# 29_LMS7002M_PowerSupply.net
KiCad netlist of a schematic drawn in Altium Designer
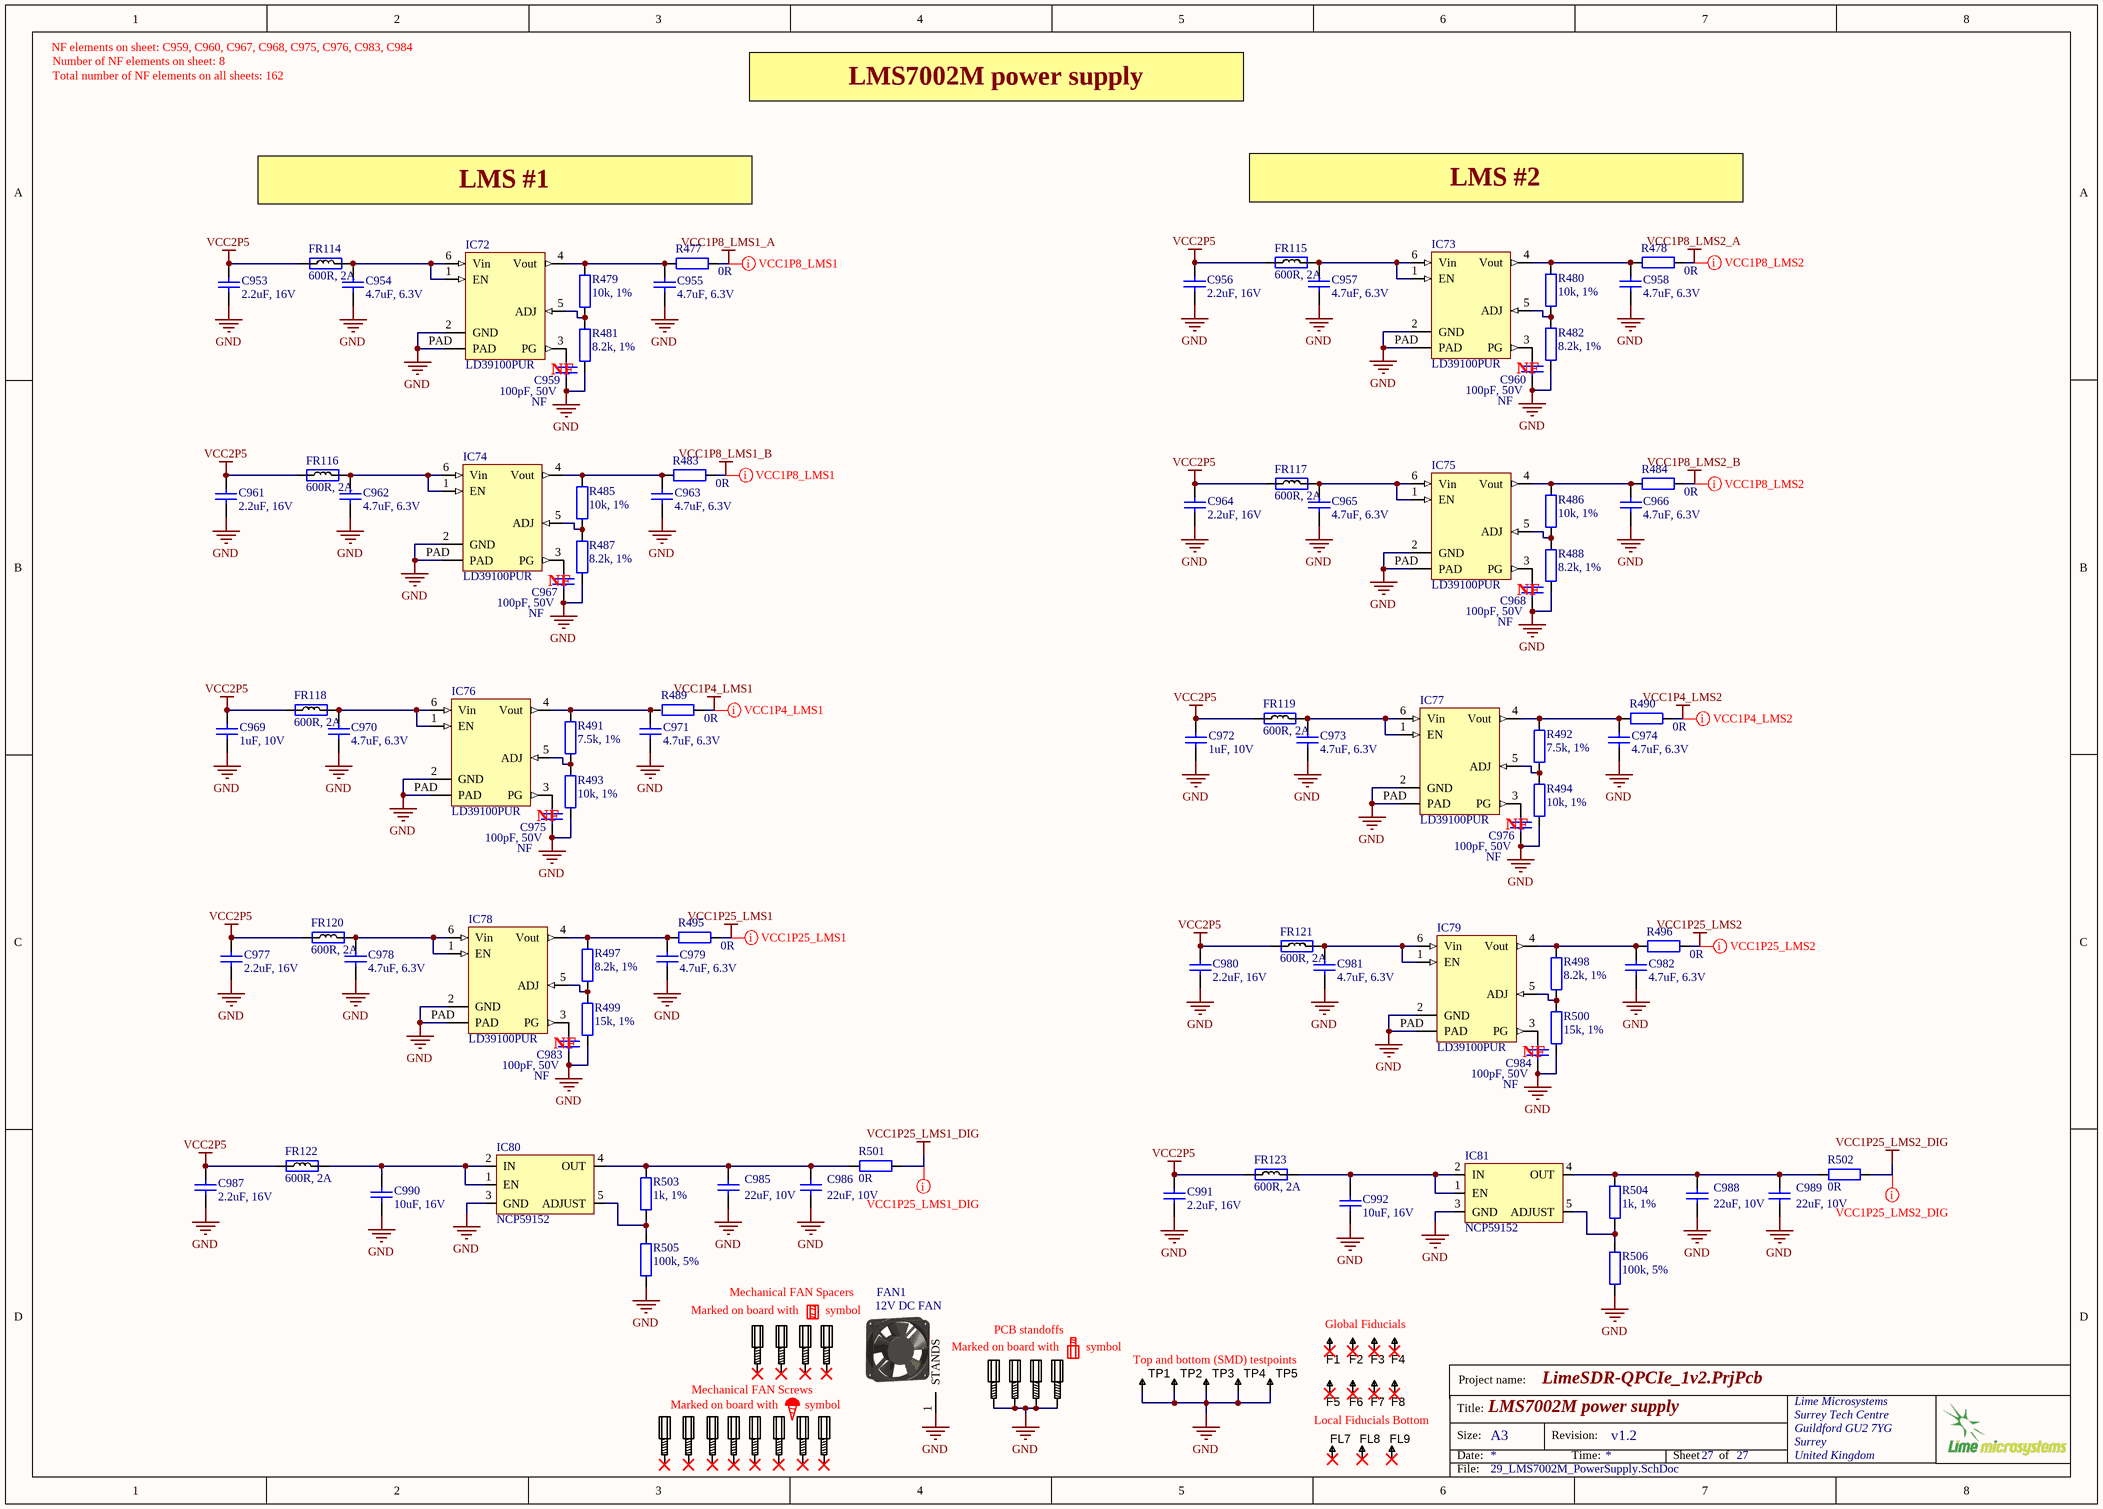
[diagram p0: 29_LMS7002M_PowerSupply.SchDoc]

(export (version "E")
  (design (tool "Eeschema 10.0.6"))
  (components
    (comp (ref "C953")
      (value "2.2uF, 16V")
      (footprint "CAP0402")
      (description "CAP CER 2.2UF 16V 10% X5R 0402")
      (fields (field (name "MANUFACTURER") "TDK Corporation") (field (name "TOLERANCE") "±20%"))
      (libsource (lib "LimeMicroAltiumLib_schLib") (part "Cap_0402"))
    )
    (comp (ref "C954")
      (value "4.7uF, 6.3V")
      (footprint "CAP0402")
      (fields
        (field (name "MANUFACTURER") "Murata Electronics North America")
        (field (name "TOLERANCE") "±20%")
        (field (name "MANUFACTURER PART NUMBER") "GRM155R60J475ME87D")
      )
      (libsource (lib "LimeMicroAltiumLib_schLib") (part "Cap_0402"))
    )
    (comp (ref "C955")
      (value "4.7uF, 6.3V")
      (footprint "CAP0402")
      (fields
        (field (name "MANUFACTURER") "Murata Electronics North America")
        (field (name "TOLERANCE") "±20%")
        (field (name "MANUFACTURER PART NUMBER") "GRM155R60J475ME87D")
      )
      (libsource (lib "LimeMicroAltiumLib_schLib") (part "Cap_0402"))
    )
    (comp (ref "C956")
      (value "2.2uF, 16V")
      (footprint "CAP0402")
      (description "CAP CER 2.2UF 16V 10% X5R 0402")
      (fields (field (name "MANUFACTURER") "TDK Corporation") (field (name "TOLERANCE") "±20%"))
      (libsource (lib "LimeMicroAltiumLib_schLib") (part "Cap_0402"))
    )
    (comp (ref "C957")
      (value "4.7uF, 6.3V")
      (footprint "CAP0402")
      (fields
        (field (name "MANUFACTURER") "Murata Electronics North America")
        (field (name "TOLERANCE") "±20%")
        (field (name "MANUFACTURER PART NUMBER") "GRM155R60J475ME87D")
      )
      (libsource (lib "LimeMicroAltiumLib_schLib") (part "Cap_0402"))
    )
    (comp (ref "C958")
      (value "4.7uF, 6.3V")
      (footprint "CAP0402")
      (fields
        (field (name "MANUFACTURER") "Murata Electronics North America")
        (field (name "TOLERANCE") "±20%")
        (field (name "MANUFACTURER PART NUMBER") "GRM155R60J475ME87D")
      )
      (libsource (lib "LimeMicroAltiumLib_schLib") (part "Cap_0402"))
    )
    (comp (ref "C959")
      (value "100pF, 50V")
      (footprint "CAP0402")
      (fields
        (field (name "ASSEMBLY INFO") "NF")
        (field (name "MANUFACTURER") "Yageo")
        (field (name "TOLERANCE") "±5%")
      )
      (libsource (lib "LimeMicroAltiumLib_schLib") (part "Cap_0402"))
    )
    (comp (ref "C960")
      (value "100pF, 50V")
      (footprint "CAP0402")
      (fields
        (field (name "ASSEMBLY INFO") "NF")
        (field (name "MANUFACTURER") "Yageo")
        (field (name "TOLERANCE") "±5%")
      )
      (libsource (lib "LimeMicroAltiumLib_schLib") (part "Cap_0402"))
    )
    (comp (ref "C961")
      (value "2.2uF, 16V")
      (footprint "CAP0402")
      (description "CAP CER 2.2UF 16V 10% X5R 0402")
      (fields (field (name "MANUFACTURER") "TDK Corporation") (field (name "TOLERANCE") "±20%"))
      (libsource (lib "LimeMicroAltiumLib_schLib") (part "Cap_0402"))
    )
    (comp (ref "C962")
      (value "4.7uF, 6.3V")
      (footprint "CAP0402")
      (fields
        (field (name "MANUFACTURER") "Murata Electronics North America")
        (field (name "TOLERANCE") "±20%")
        (field (name "MANUFACTURER PART NUMBER") "GRM155R60J475ME87D")
      )
      (libsource (lib "LimeMicroAltiumLib_schLib") (part "Cap_0402"))
    )
    (comp (ref "C963")
      (value "4.7uF, 6.3V")
      (footprint "CAP0402")
      (fields
        (field (name "MANUFACTURER") "Murata Electronics North America")
        (field (name "TOLERANCE") "±20%")
        (field (name "MANUFACTURER PART NUMBER") "GRM155R60J475ME87D")
      )
      (libsource (lib "LimeMicroAltiumLib_schLib") (part "Cap_0402"))
    )
    (comp (ref "C964")
      (value "2.2uF, 16V")
      (footprint "CAP0402")
      (description "CAP CER 2.2UF 16V 10% X5R 0402")
      (fields (field (name "MANUFACTURER") "TDK Corporation") (field (name "TOLERANCE") "±20%"))
      (libsource (lib "LimeMicroAltiumLib_schLib") (part "Cap_0402"))
    )
    (comp (ref "C965")
      (value "4.7uF, 6.3V")
      (footprint "CAP0402")
      (fields
        (field (name "MANUFACTURER") "Murata Electronics North America")
        (field (name "TOLERANCE") "±20%")
        (field (name "MANUFACTURER PART NUMBER") "GRM155R60J475ME87D")
      )
      (libsource (lib "LimeMicroAltiumLib_schLib") (part "Cap_0402"))
    )
    (comp (ref "C966")
      (value "4.7uF, 6.3V")
      (footprint "CAP0402")
      (fields
        (field (name "MANUFACTURER") "Murata Electronics North America")
        (field (name "TOLERANCE") "±20%")
        (field (name "MANUFACTURER PART NUMBER") "GRM155R60J475ME87D")
      )
      (libsource (lib "LimeMicroAltiumLib_schLib") (part "Cap_0402"))
    )
    (comp (ref "C967")
      (value "100pF, 50V")
      (footprint "CAP0402")
      (fields
        (field (name "ASSEMBLY INFO") "NF")
        (field (name "MANUFACTURER") "Yageo")
        (field (name "TOLERANCE") "±5%")
      )
      (libsource (lib "LimeMicroAltiumLib_schLib") (part "Cap_0402"))
    )
    (comp (ref "C968")
      (value "100pF, 50V")
      (footprint "CAP0402")
      (fields
        (field (name "ASSEMBLY INFO") "NF")
        (field (name "MANUFACTURER") "Yageo")
        (field (name "TOLERANCE") "±5%")
      )
      (libsource (lib "LimeMicroAltiumLib_schLib") (part "Cap_0402"))
    )
    (comp (ref "C969")
      (value "1uF, 10V")
      (footprint "CAP0402")
      (fields (field (name "MANUFACTURER") "TDK"))
      (libsource (lib "LimeMicroAltiumLib_schLib") (part "Cap_0402"))
    )
    (comp (ref "C970")
      (value "4.7uF, 6.3V")
      (footprint "CAP0402")
      (fields
        (field (name "MANUFACTURER") "Murata Electronics North America")
        (field (name "TOLERANCE") "±20%")
        (field (name "MANUFACTURER PART NUMBER") "GRM155R60J475ME87D")
      )
      (libsource (lib "LimeMicroAltiumLib_schLib") (part "Cap_0402"))
    )
    (comp (ref "C971")
      (value "4.7uF, 6.3V")
      (footprint "CAP0402")
      (fields
        (field (name "MANUFACTURER") "Murata Electronics North America")
        (field (name "TOLERANCE") "±20%")
        (field (name "MANUFACTURER PART NUMBER") "GRM155R60J475ME87D")
      )
      (libsource (lib "LimeMicroAltiumLib_schLib") (part "Cap_0402"))
    )
    (comp (ref "C972")
      (value "1uF, 10V")
      (footprint "CAP0402")
      (fields (field (name "MANUFACTURER") "TDK"))
      (libsource (lib "LimeMicroAltiumLib_schLib") (part "Cap_0402"))
    )
    (comp (ref "C973")
      (value "4.7uF, 6.3V")
      (footprint "CAP0402")
      (fields
        (field (name "MANUFACTURER") "Murata Electronics North America")
        (field (name "TOLERANCE") "±20%")
        (field (name "MANUFACTURER PART NUMBER") "GRM155R60J475ME87D")
      )
      (libsource (lib "LimeMicroAltiumLib_schLib") (part "Cap_0402"))
    )
    (comp (ref "C974")
      (value "4.7uF, 6.3V")
      (footprint "CAP0402")
      (fields
        (field (name "MANUFACTURER") "Murata Electronics North America")
        (field (name "TOLERANCE") "±20%")
        (field (name "MANUFACTURER PART NUMBER") "GRM155R60J475ME87D")
      )
      (libsource (lib "LimeMicroAltiumLib_schLib") (part "Cap_0402"))
    )
    (comp (ref "C975")
      (value "100pF, 50V")
      (footprint "CAP0402")
      (fields
        (field (name "ASSEMBLY INFO") "NF")
        (field (name "MANUFACTURER") "Yageo")
        (field (name "TOLERANCE") "±5%")
      )
      (libsource (lib "LimeMicroAltiumLib_schLib") (part "Cap_0402"))
    )
    (comp (ref "C976")
      (value "100pF, 50V")
      (footprint "CAP0402")
      (fields
        (field (name "ASSEMBLY INFO") "NF")
        (field (name "MANUFACTURER") "Yageo")
        (field (name "TOLERANCE") "±5%")
      )
      (libsource (lib "LimeMicroAltiumLib_schLib") (part "Cap_0402"))
    )
    (comp (ref "C977")
      (value "2.2uF, 16V")
      (footprint "CAP0402")
      (description "CAP CER 2.2UF 16V 10% X5R 0402")
      (fields (field (name "MANUFACTURER") "TDK Corporation") (field (name "TOLERANCE") "±20%"))
      (libsource (lib "LimeMicroAltiumLib_schLib") (part "Cap_0402"))
    )
    (comp (ref "C978")
      (value "4.7uF, 6.3V")
      (footprint "CAP0402")
      (fields
        (field (name "MANUFACTURER") "Murata Electronics North America")
        (field (name "TOLERANCE") "±20%")
        (field (name "MANUFACTURER PART NUMBER") "GRM155R60J475ME87D")
      )
      (libsource (lib "LimeMicroAltiumLib_schLib") (part "Cap_0402"))
    )
    (comp (ref "C979")
      (value "4.7uF, 6.3V")
      (footprint "CAP0402")
      (fields
        (field (name "MANUFACTURER") "Murata Electronics North America")
        (field (name "TOLERANCE") "±20%")
        (field (name "MANUFACTURER PART NUMBER") "GRM155R60J475ME87D")
      )
      (libsource (lib "LimeMicroAltiumLib_schLib") (part "Cap_0402"))
    )
    (comp (ref "C980")
      (value "2.2uF, 16V")
      (footprint "CAP0402")
      (description "CAP CER 2.2UF 16V 10% X5R 0402")
      (fields (field (name "MANUFACTURER") "TDK Corporation") (field (name "TOLERANCE") "±20%"))
      (libsource (lib "LimeMicroAltiumLib_schLib") (part "Cap_0402"))
    )
    (comp (ref "C981")
      (value "4.7uF, 6.3V")
      (footprint "CAP0402")
      (fields
        (field (name "MANUFACTURER") "Murata Electronics North America")
        (field (name "TOLERANCE") "±20%")
        (field (name "MANUFACTURER PART NUMBER") "GRM155R60J475ME87D")
      )
      (libsource (lib "LimeMicroAltiumLib_schLib") (part "Cap_0402"))
    )
    (comp (ref "C982")
      (value "4.7uF, 6.3V")
      (footprint "CAP0402")
      (fields
        (field (name "MANUFACTURER") "Murata Electronics North America")
        (field (name "TOLERANCE") "±20%")
        (field (name "MANUFACTURER PART NUMBER") "GRM155R60J475ME87D")
      )
      (libsource (lib "LimeMicroAltiumLib_schLib") (part "Cap_0402"))
    )
    (comp (ref "C983")
      (value "100pF, 50V")
      (footprint "CAP0402")
      (fields
        (field (name "ASSEMBLY INFO") "NF")
        (field (name "MANUFACTURER") "Yageo")
        (field (name "TOLERANCE") "±5%")
      )
      (libsource (lib "LimeMicroAltiumLib_schLib") (part "Cap_0402"))
    )
    (comp (ref "C984")
      (value "100pF, 50V")
      (footprint "CAP0402")
      (fields
        (field (name "ASSEMBLY INFO") "NF")
        (field (name "MANUFACTURER") "Yageo")
        (field (name "TOLERANCE") "±5%")
      )
      (libsource (lib "LimeMicroAltiumLib_schLib") (part "Cap_0402"))
    )
    (comp (ref "C985")
      (value "22uF, 10V")
      (footprint "CAP0603")
      (fields (field (name "TOLERANCE") "20 %") (field (name "MANUFACTURER") "TDK Corporation"))
      (libsource (lib "LimeFPGAboard_schLib") (part "Cap_0603"))
    )
    (comp (ref "C986")
      (value "22uF, 10V")
      (footprint "CAP0603")
      (fields (field (name "TOLERANCE") "20 %") (field (name "MANUFACTURER") "TDK Corporation"))
      (libsource (lib "LimeFPGAboard_schLib") (part "Cap_0603"))
    )
    (comp (ref "C987")
      (value "2.2uF, 16V")
      (footprint "CAP0402")
      (description "CAP CER 2.2UF 16V 10% X5R 0402")
      (fields (field (name "MANUFACTURER") "TDK Corporation") (field (name "TOLERANCE") "±20%"))
      (libsource (lib "LimeMicroAltiumLib_schLib") (part "Cap_0402"))
    )
    (comp (ref "C988")
      (value "22uF, 10V")
      (footprint "CAP0603")
      (fields (field (name "TOLERANCE") "20 %") (field (name "MANUFACTURER") "TDK Corporation"))
      (libsource (lib "LimeFPGAboard_schLib") (part "Cap_0603"))
    )
    (comp (ref "C989")
      (value "22uF, 10V")
      (footprint "CAP0603")
      (fields (field (name "TOLERANCE") "20 %") (field (name "MANUFACTURER") "TDK Corporation"))
      (libsource (lib "LimeFPGAboard_schLib") (part "Cap_0603"))
    )
    (comp (ref "C990")
      (value "10uF, 16V")
      (footprint "CAP0603")
      (fields (field (name "MANUFACTURER") "Yageo") (field (name "TOLERANCE") "±20%"))
      (libsource (lib "LimeMicroAltiumLib_schLib") (part "Cap_0603"))
    )
    (comp (ref "C991")
      (value "2.2uF, 16V")
      (footprint "CAP0402")
      (description "CAP CER 2.2UF 16V 10% X5R 0402")
      (fields (field (name "MANUFACTURER") "TDK Corporation") (field (name "TOLERANCE") "±20%"))
      (libsource (lib "LimeMicroAltiumLib_schLib") (part "Cap_0402"))
    )
    (comp (ref "C992")
      (value "10uF, 16V")
      (footprint "CAP0603")
      (fields (field (name "MANUFACTURER") "Yageo") (field (name "TOLERANCE") "±20%"))
      (libsource (lib "LimeMicroAltiumLib_schLib") (part "Cap_0603"))
    )
    (comp (ref "F1")
      (value "Fiducial")
      (footprint "Fiducial")
      (libsource (lib "VGTU_Altium_lib") (part "Fiducial"))
    )
    (comp (ref "F2")
      (value "Fiducial")
      (footprint "Fiducial")
      (libsource (lib "VGTU_Altium_lib") (part "Fiducial"))
    )
    (comp (ref "F3")
      (value "Fiducial")
      (footprint "Fiducial")
      (libsource (lib "VGTU_Altium_lib") (part "Fiducial"))
    )
    (comp (ref "F4")
      (value "Fiducial")
      (footprint "Fiducial")
      (libsource (lib "VGTU_Altium_lib") (part "Fiducial"))
    )
    (comp (ref "F5")
      (value "Fiducial")
      (footprint "Fiducial")
      (libsource (lib "VGTU_Altium_lib") (part "Fiducial"))
    )
    (comp (ref "F6")
      (value "Fiducial")
      (footprint "Fiducial")
      (libsource (lib "VGTU_Altium_lib") (part "Fiducial"))
    )
    (comp (ref "F7")
      (value "Fiducial")
      (footprint "Fiducial")
      (libsource (lib "VGTU_Altium_lib") (part "Fiducial"))
    )
    (comp (ref "F8")
      (value "Fiducial")
      (footprint "Fiducial")
      (libsource (lib "VGTU_Altium_lib") (part "Fiducial"))
    )
    (comp (ref "FAN1")
      (value "12V DC FAN")
      (footprint "FAN_60mm_v3")
      (fields (field (name "MANUFACTURER") "Sunon Fans") (field (name ".CHECKED PCB") "AV"))
      (libsource (lib "LimeMicroAltiumLib_schLib") (part "12V_DC_FAN"))
    )
    (comp (ref "FL7")
      (value "Fiducial")
      (footprint "Fiducial_local")
      (libsource (lib "LimeMicroAltiumLib_schLib") (part "Fiducial"))
    )
    (comp (ref "FL8")
      (value "Fiducial")
      (footprint "Fiducial_local")
      (libsource (lib "LimeMicroAltiumLib_schLib") (part "Fiducial"))
    )
    (comp (ref "FL9")
      (value "Fiducial")
      (footprint "Fiducial_local")
      (libsource (lib "LimeMicroAltiumLib_schLib") (part "Fiducial"))
    )
    (comp (ref "FR114")
      (value "600R, 2A")
      (footprint "RES0805")
      (fields (field (name "MANUFACTURER") "TDK"))
      (libsource (lib "LimeMicroAltiumLib_schLib") (part "Ferrite"))
    )
    (comp (ref "FR115")
      (value "600R, 2A")
      (footprint "RES0805")
      (fields (field (name "MANUFACTURER") "TDK"))
      (libsource (lib "LimeMicroAltiumLib_schLib") (part "Ferrite"))
    )
    (comp (ref "FR116")
      (value "600R, 2A")
      (footprint "RES0805")
      (fields (field (name "MANUFACTURER") "TDK"))
      (libsource (lib "LimeMicroAltiumLib_schLib") (part "Ferrite"))
    )
    (comp (ref "FR117")
      (value "600R, 2A")
      (footprint "RES0805")
      (fields (field (name "MANUFACTURER") "TDK"))
      (libsource (lib "LimeMicroAltiumLib_schLib") (part "Ferrite"))
    )
    (comp (ref "FR118")
      (value "600R, 2A")
      (footprint "RES0805")
      (fields (field (name "MANUFACTURER") "TDK"))
      (libsource (lib "LimeMicroAltiumLib_schLib") (part "Ferrite"))
    )
    (comp (ref "FR119")
      (value "600R, 2A")
      (footprint "RES0805")
      (fields (field (name "MANUFACTURER") "TDK"))
      (libsource (lib "LimeMicroAltiumLib_schLib") (part "Ferrite"))
    )
    (comp (ref "FR120")
      (value "600R, 2A")
      (footprint "RES0805")
      (fields (field (name "MANUFACTURER") "TDK"))
      (libsource (lib "LimeMicroAltiumLib_schLib") (part "Ferrite"))
    )
    (comp (ref "FR121")
      (value "600R, 2A")
      (footprint "RES0805")
      (fields (field (name "MANUFACTURER") "TDK"))
      (libsource (lib "LimeMicroAltiumLib_schLib") (part "Ferrite"))
    )
    (comp (ref "FR122")
      (value "600R, 2A")
      (footprint "RES0805")
      (fields (field (name "MANUFACTURER") "TDK"))
      (libsource (lib "LimeMicroAltiumLib_schLib") (part "Ferrite"))
    )
    (comp (ref "FR123")
      (value "600R, 2A")
      (footprint "RES0805")
      (fields (field (name "MANUFACTURER") "TDK"))
      (libsource (lib "LimeMicroAltiumLib_schLib") (part "Ferrite"))
    )
    (comp (ref "IC72")
      (value "LD39100PUR")
      (footprint "LD39100PUR")
      (fields (field (name "MANUFACTURER") "STMicroelectronics"))
      (libsource (lib "LimeMicroAltiumLib_schLib") (part "LD39100PUR"))
    )
    (comp (ref "IC73")
      (value "LD39100PUR")
      (footprint "LD39100PUR")
      (fields (field (name "MANUFACTURER") "STMicroelectronics"))
      (libsource (lib "LimeMicroAltiumLib_schLib") (part "LD39100PUR"))
    )
    (comp (ref "IC74")
      (value "LD39100PUR")
      (footprint "LD39100PUR")
      (fields (field (name "MANUFACTURER") "STMicroelectronics"))
      (libsource (lib "LimeMicroAltiumLib_schLib") (part "LD39100PUR"))
    )
    (comp (ref "IC75")
      (value "LD39100PUR")
      (footprint "LD39100PUR")
      (fields (field (name "MANUFACTURER") "STMicroelectronics"))
      (libsource (lib "LimeMicroAltiumLib_schLib") (part "LD39100PUR"))
    )
    (comp (ref "IC76")
      (value "LD39100PUR")
      (footprint "LD39100PUR")
      (fields (field (name "MANUFACTURER") "STMicroelectronics"))
      (libsource (lib "LimeMicroAltiumLib_schLib") (part "LD39100PUR"))
    )
    (comp (ref "IC77")
      (value "LD39100PUR")
      (footprint "LD39100PUR")
      (fields (field (name "MANUFACTURER") "STMicroelectronics"))
      (libsource (lib "LimeMicroAltiumLib_schLib") (part "LD39100PUR"))
    )
    (comp (ref "IC78")
      (value "LD39100PUR")
      (footprint "LD39100PUR")
      (fields (field (name "MANUFACTURER") "STMicroelectronics"))
      (libsource (lib "LimeMicroAltiumLib_schLib") (part "LD39100PUR"))
    )
    (comp (ref "IC79")
      (value "LD39100PUR")
      (footprint "LD39100PUR")
      (fields (field (name "MANUFACTURER") "STMicroelectronics"))
      (libsource (lib "LimeMicroAltiumLib_schLib") (part "LD39100PUR"))
    )
    (comp (ref "IC80")
      (value "NCP59152")
      (footprint "TO-263-5")
      (fields
        (field (name "MANUFACTURER PART NUMBER") "NCP59152DSADJR4G")
        (field (name "MANUFACTURER") "ON Semiconductor")
      )
      (libsource (lib "LimeMicroAltiumLib_schLib") (part "NCP59151"))
    )
    (comp (ref "IC81")
      (value "NCP59152")
      (footprint "TO-263-5")
      (fields
        (field (name "MANUFACTURER PART NUMBER") "NCP59152DSADJR4G")
        (field (name "MANUFACTURER") "ON Semiconductor")
      )
      (libsource (lib "LimeMicroAltiumLib_schLib") (part "NCP59151"))
    )
    (comp (ref "MECH22")
      (value "Spacer M3")
      (description "STANDOFF M/F MET 5MM HEX 10MM L")
      (fields (field (name "MANUFACTURER") "BOSSARD"))
      (libsource (lib "LimeMicroAltiumLib_schLib") (part "STANDOFF_M-F_THREADED_M3x8x10mm_HEX_5mm dia"))
    )
    (comp (ref "MECH23")
      (value "Spacer M3")
      (description "STANDOFF M/F MET 5MM HEX 10MM L")
      (fields (field (name "MANUFACTURER") "BOSSARD"))
      (libsource (lib "LimeMicroAltiumLib_schLib") (part "STANDOFF_M-F_THREADED_M3x8x10mm_HEX_5mm dia"))
    )
    (comp (ref "MECH24")
      (value "Spacer M3")
      (description "STANDOFF M/F MET 5MM HEX 10MM L")
      (fields (field (name "MANUFACTURER") "BOSSARD"))
      (libsource (lib "LimeMicroAltiumLib_schLib") (part "STANDOFF_M-F_THREADED_M3x8x10mm_HEX_5mm dia"))
    )
    (comp (ref "MECH25")
      (value "Spacer M3")
      (description "STANDOFF M/F MET 5MM HEX 10MM L")
      (fields (field (name "MANUFACTURER") "BOSSARD"))
      (libsource (lib "LimeMicroAltiumLib_schLib") (part "STANDOFF_M-F_THREADED_M3x8x10mm_HEX_5mm dia"))
    )
    (comp (ref "MECH26")
      (value "# pcs.")
      (footprint "PCB_standoff")
      (description "STANDOFF M/F MET 5MM HEX 10MM L")
      (fields (field (name "MANUFACTURER") "Keystone Electronics"))
      (libsource (lib "LimeMicroAltiumLib_schLib") (part "STANDOFF_M-F_THREADED_M3x8x10mm_HEX_5mm dia"))
    )
    (comp (ref "MECH27")
      (value "# pcs.")
      (footprint "PCB_standoff")
      (description "STANDOFF M/F MET 5MM HEX 10MM L")
      (fields (field (name "MANUFACTURER") "Keystone Electronics"))
      (libsource (lib "LimeMicroAltiumLib_schLib") (part "STANDOFF_M-F_THREADED_M3x8x10mm_HEX_5mm dia"))
    )
    (comp (ref "MECH28")
      (value "Screws M3")
      (description "STANDOFF M/F MET 5MM HEX 10MM L")
      (fields (field (name "MANUFACTURER") "BOSSARD"))
      (libsource (lib "LimeMicroAltiumLib_schLib") (part "STANDOFF_M-F_THREADED_M3x8x10mm_HEX_5mm dia"))
    )
    (comp (ref "MECH29")
      (value "Screws M3")
      (description "STANDOFF M/F MET 5MM HEX 10MM L")
      (fields (field (name "MANUFACTURER") "BOSSARD"))
      (libsource (lib "LimeMicroAltiumLib_schLib") (part "STANDOFF_M-F_THREADED_M3x8x10mm_HEX_5mm dia"))
    )
    (comp (ref "MECH30")
      (value "Screws M3")
      (description "STANDOFF M/F MET 5MM HEX 10MM L")
      (fields (field (name "MANUFACTURER") "BOSSARD"))
      (libsource (lib "LimeMicroAltiumLib_schLib") (part "STANDOFF_M-F_THREADED_M3x8x10mm_HEX_5mm dia"))
    )
    (comp (ref "MECH31")
      (value "Screws M3")
      (description "STANDOFF M/F MET 5MM HEX 10MM L")
      (fields (field (name "MANUFACTURER") "BOSSARD"))
      (libsource (lib "LimeMicroAltiumLib_schLib") (part "STANDOFF_M-F_THREADED_M3x8x10mm_HEX_5mm dia"))
    )
    (comp (ref "MECH32")
      (value "Screws M3")
      (description "STANDOFF M/F MET 5MM HEX 10MM L")
      (fields (field (name "MANUFACTURER") "BOSSARD"))
      (libsource (lib "LimeMicroAltiumLib_schLib") (part "STANDOFF_M-F_THREADED_M3x8x10mm_HEX_5mm dia"))
    )
    (comp (ref "MECH33")
      (value "Screws M3")
      (description "STANDOFF M/F MET 5MM HEX 10MM L")
      (fields (field (name "MANUFACTURER") "BOSSARD"))
      (libsource (lib "LimeMicroAltiumLib_schLib") (part "STANDOFF_M-F_THREADED_M3x8x10mm_HEX_5mm dia"))
    )
    (comp (ref "MECH34")
      (value "Screws M3")
      (description "STANDOFF M/F MET 5MM HEX 10MM L")
      (fields (field (name "MANUFACTURER") "BOSSARD"))
      (libsource (lib "LimeMicroAltiumLib_schLib") (part "STANDOFF_M-F_THREADED_M3x8x10mm_HEX_5mm dia"))
    )
    (comp (ref "MECH35")
      (value "Screws M3")
      (description "STANDOFF M/F MET 5MM HEX 10MM L")
      (fields (field (name "MANUFACTURER") "BOSSARD"))
      (libsource (lib "LimeMicroAltiumLib_schLib") (part "STANDOFF_M-F_THREADED_M3x8x10mm_HEX_5mm dia"))
    )
    (comp (ref "MECH36")
      (value "# pcs.")
      (footprint "PCB_standoff")
      (description "STANDOFF M/F MET 5MM HEX 10MM L")
      (fields (field (name "MANUFACTURER") "Keystone Electronics"))
      (libsource (lib "LimeMicroAltiumLib_schLib") (part "STANDOFF_M-F_THREADED_M3x8x10mm_HEX_5mm dia"))
    )
    (comp (ref "MECH37")
      (value "# pcs.")
      (footprint "PCB_standoff")
      (description "STANDOFF M/F MET 5MM HEX 10MM L")
      (fields (field (name "MANUFACTURER") "Keystone Electronics"))
      (libsource (lib "LimeMicroAltiumLib_schLib") (part "STANDOFF_M-F_THREADED_M3x8x10mm_HEX_5mm dia"))
    )
    (comp (ref "R477")
      (value "0R")
      (footprint "RES0402")
      (fields (field (name "MANUFACTURER") "Yageo") (field (name "TOLERANCE") "Jumper"))
      (libsource (lib "LimeMicroAltiumLib_schLib") (part "Res_0402"))
    )
    (comp (ref "R478")
      (value "0R")
      (footprint "RES0402")
      (fields (field (name "MANUFACTURER") "Yageo") (field (name "TOLERANCE") "Jumper"))
      (libsource (lib "LimeMicroAltiumLib_schLib") (part "Res_0402"))
    )
    (comp (ref "R479")
      (value "10k, 1%")
      (footprint "RES0402")
      (fields (field (name "MANUFACTURER") "Yageo") (field (name "TOLERANCE") "±1%"))
      (libsource (lib "LimeMicroAltiumLib_schLib") (part "Res_0402"))
    )
    (comp (ref "R480")
      (value "10k, 1%")
      (footprint "RES0402")
      (fields (field (name "MANUFACTURER") "Yageo") (field (name "TOLERANCE") "±1%"))
      (libsource (lib "LimeMicroAltiumLib_schLib") (part "Res_0402"))
    )
    (comp (ref "R481")
      (value "8.2k, 1%")
      (footprint "RES0402")
      (fields (field (name "MANUFACTURER") "Yageo") (field (name "TOLERANCE") "±1%"))
      (libsource (lib "LimeMicroAltiumLib_schLib") (part "Res_0402"))
    )
    (comp (ref "R482")
      (value "8.2k, 1%")
      (footprint "RES0402")
      (fields (field (name "MANUFACTURER") "Yageo") (field (name "TOLERANCE") "±1%"))
      (libsource (lib "LimeMicroAltiumLib_schLib") (part "Res_0402"))
    )
    (comp (ref "R483")
      (value "0R")
      (footprint "RES0402")
      (fields (field (name "MANUFACTURER") "Yageo") (field (name "TOLERANCE") "Jumper"))
      (libsource (lib "LimeMicroAltiumLib_schLib") (part "Res_0402"))
    )
    (comp (ref "R484")
      (value "0R")
      (footprint "RES0402")
      (fields (field (name "MANUFACTURER") "Yageo") (field (name "TOLERANCE") "Jumper"))
      (libsource (lib "LimeMicroAltiumLib_schLib") (part "Res_0402"))
    )
    (comp (ref "R485")
      (value "10k, 1%")
      (footprint "RES0402")
      (fields (field (name "MANUFACTURER") "Yageo") (field (name "TOLERANCE") "±1%"))
      (libsource (lib "LimeMicroAltiumLib_schLib") (part "Res_0402"))
    )
    (comp (ref "R486")
      (value "10k, 1%")
      (footprint "RES0402")
      (fields (field (name "MANUFACTURER") "Yageo") (field (name "TOLERANCE") "±1%"))
      (libsource (lib "LimeMicroAltiumLib_schLib") (part "Res_0402"))
    )
    (comp (ref "R487")
      (value "8.2k, 1%")
      (footprint "RES0402")
      (fields (field (name "MANUFACTURER") "Yageo") (field (name "TOLERANCE") "±1%"))
      (libsource (lib "LimeMicroAltiumLib_schLib") (part "Res_0402"))
    )
    (comp (ref "R488")
      (value "8.2k, 1%")
      (footprint "RES0402")
      (fields (field (name "MANUFACTURER") "Yageo") (field (name "TOLERANCE") "±1%"))
      (libsource (lib "LimeMicroAltiumLib_schLib") (part "Res_0402"))
    )
    (comp (ref "R489")
      (value "0R")
      (footprint "RES0402")
      (fields (field (name "MANUFACTURER") "Yageo") (field (name "TOLERANCE") "Jumper"))
      (libsource (lib "LimeMicroAltiumLib_schLib") (part "Res_0402"))
    )
    (comp (ref "R490")
      (value "0R")
      (footprint "RES0402")
      (fields (field (name "MANUFACTURER") "Yageo") (field (name "TOLERANCE") "Jumper"))
      (libsource (lib "LimeMicroAltiumLib_schLib") (part "Res_0402"))
    )
    (comp (ref "R491")
      (value "7.5k, 1%")
      (footprint "RES0402")
      (fields
        (field (name "MANUFACTURER") "Yageo")
        (field (name "TOLERANCE") "±1%")
        (field (name "MANUFACTURER PART NUMBER") "RC0402FR-077K5L")
      )
      (libsource (lib "LimeMicroAltiumLib_schLib") (part "Res_0402"))
    )
    (comp (ref "R492")
      (value "7.5k, 1%")
      (footprint "RES0402")
      (fields
        (field (name "MANUFACTURER") "Yageo")
        (field (name "TOLERANCE") "±1%")
        (field (name "MANUFACTURER PART NUMBER") "RC0402FR-077K5L")
      )
      (libsource (lib "LimeMicroAltiumLib_schLib") (part "Res_0402"))
    )
    (comp (ref "R493")
      (value "10k, 1%")
      (footprint "RES0402")
      (fields (field (name "MANUFACTURER") "Yageo") (field (name "TOLERANCE") "±1%"))
      (libsource (lib "LimeMicroAltiumLib_schLib") (part "Res_0402"))
    )
    (comp (ref "R494")
      (value "10k, 1%")
      (footprint "RES0402")
      (fields (field (name "MANUFACTURER") "Yageo") (field (name "TOLERANCE") "±1%"))
      (libsource (lib "LimeMicroAltiumLib_schLib") (part "Res_0402"))
    )
    (comp (ref "R495")
      (value "0R")
      (footprint "RES0402")
      (fields (field (name "MANUFACTURER") "Yageo") (field (name "TOLERANCE") "Jumper"))
      (libsource (lib "LimeMicroAltiumLib_schLib") (part "Res_0402"))
    )
    (comp (ref "R496")
      (value "0R")
      (footprint "RES0402")
      (fields (field (name "MANUFACTURER") "Yageo") (field (name "TOLERANCE") "Jumper"))
      (libsource (lib "LimeMicroAltiumLib_schLib") (part "Res_0402"))
    )
    (comp (ref "R497")
      (value "8.2k, 1%")
      (footprint "RES0402")
      (fields (field (name "MANUFACTURER") "Yageo") (field (name "TOLERANCE") "±1%"))
      (libsource (lib "LimeMicroAltiumLib_schLib") (part "Res_0402"))
    )
    (comp (ref "R498")
      (value "8.2k, 1%")
      (footprint "RES0402")
      (fields (field (name "MANUFACTURER") "Yageo") (field (name "TOLERANCE") "±1%"))
      (libsource (lib "LimeMicroAltiumLib_schLib") (part "Res_0402"))
    )
    (comp (ref "R499")
      (value "15k, 1%")
      (footprint "RES0402")
      (fields (field (name "TOLERANCE") "±1%") (field (name "MANUFACTURER") "Yageo"))
      (libsource (lib "LimeMicroAltiumLib_schLib") (part "Res_0402"))
    )
    (comp (ref "R500")
      (value "15k, 1%")
      (footprint "RES0402")
      (fields (field (name "TOLERANCE") "±1%") (field (name "MANUFACTURER") "Yageo"))
      (libsource (lib "LimeMicroAltiumLib_schLib") (part "Res_0402"))
    )
    (comp (ref "R501")
      (value "0R")
      (footprint "RES0402")
      (fields (field (name "MANUFACTURER") "Yageo") (field (name "TOLERANCE") "Jumper"))
      (libsource (lib "LimeMicroAltiumLib_schLib") (part "Res_0402"))
    )
    (comp (ref "R502")
      (value "0R")
      (footprint "RES0402")
      (fields (field (name "MANUFACTURER") "Yageo") (field (name "TOLERANCE") "Jumper"))
      (libsource (lib "LimeMicroAltiumLib_schLib") (part "Res_0402"))
    )
    (comp (ref "R503")
      (value "1k, 1%")
      (footprint "RES0402")
      (fields (field (name "MANUFACTURER") "Stackpole Electronics Inc") (field (name "TOLERANCE") "±1%"))
      (libsource (lib "LimeMicroAltiumLib_schLib") (part "Res_0402"))
    )
    (comp (ref "R504")
      (value "1k, 1%")
      (footprint "RES0402")
      (fields (field (name "MANUFACTURER") "Stackpole Electronics Inc") (field (name "TOLERANCE") "±1%"))
      (libsource (lib "LimeMicroAltiumLib_schLib") (part "Res_0402"))
    )
    (comp (ref "R505")
      (value "100k, 5%")
      (footprint "RES0402")
      (fields
        (field (name "MANUFACTURER") "Panasonic Electronic Components")
        (field (name "TOLERANCE") "±5%")
      )
      (libsource (lib "LimeMicroAltiumLib_schLib") (part "Res_0402"))
    )
    (comp (ref "R506")
      (value "100k, 5%")
      (footprint "RES0402")
      (fields
        (field (name "MANUFACTURER") "Panasonic Electronic Components")
        (field (name "TOLERANCE") "±5%")
      )
      (libsource (lib "LimeMicroAltiumLib_schLib") (part "Res_0402"))
    )
    (comp (ref "TP1")
      (value "TESTPOINT_THT_MINI")
      (footprint "TP-SMD-LOW_PROFILE")
      (description "Test Point PCB mount Miniature White")
      (fields (field (name "MANUFACTURER") "Harwin Inc"))
      (libsource (lib "LimeMicroAltiumLib_schLib") (part "TESTPOINT_THT_MINI"))
    )
    (comp (ref "TP2")
      (value "TESTPOINT_THT_MINI")
      (footprint "TP-SMD-LOW_PROFILE")
      (description "Test Point PCB mount Miniature White")
      (fields (field (name "MANUFACTURER") "Harwin Inc"))
      (libsource (lib "LimeMicroAltiumLib_schLib") (part "TESTPOINT_THT_MINI"))
    )
    (comp (ref "TP3")
      (value "TESTPOINT_THT_MINI")
      (footprint "TP-SMD-LOW_PROFILE")
      (description "Test Point PCB mount Miniature White")
      (fields (field (name "MANUFACTURER") "Harwin Inc"))
      (libsource (lib "LimeMicroAltiumLib_schLib") (part "TESTPOINT_THT_MINI"))
    )
    (comp (ref "TP4")
      (value "TESTPOINT_THT_MINI")
      (footprint "TP-SMD-LOW_PROFILE")
      (description "Test Point PCB mount Miniature White")
      (fields (field (name "MANUFACTURER") "Harwin Inc"))
      (libsource (lib "LimeMicroAltiumLib_schLib") (part "TESTPOINT_THT_MINI"))
    )
    (comp (ref "TP5")
      (value "TESTPOINT_THT_MINI")
      (footprint "TP-SMD-LOW_PROFILE")
      (description "Test Point PCB mount Miniature White")
      (fields (field (name "MANUFACTURER") "Harwin Inc"))
      (libsource (lib "LimeMicroAltiumLib_schLib") (part "TESTPOINT_THT_MINI"))
    )
  )
  (nets
    (net (code "1") (name "GND") (class "Default")
      (node (ref "C953") (pin "1") (pinfunction "1_1") (pintype "passive"))
      (node (ref "C954") (pin "1") (pinfunction "1_1") (pintype "passive"))
      (node (ref "C955") (pin "1") (pinfunction "1_1") (pintype "passive"))
      (node (ref "C956") (pin "1") (pinfunction "1_1") (pintype "passive"))
      (node (ref "C957") (pin "1") (pinfunction "1_1") (pintype "passive"))
      (node (ref "C958") (pin "1") (pinfunction "1_1") (pintype "passive"))
      (node (ref "C959") (pin "1") (pinfunction "1_1") (pintype "passive"))
      (node (ref "C960") (pin "1") (pinfunction "1_1") (pintype "passive"))
      (node (ref "C961") (pin "1") (pinfunction "1_1") (pintype "passive"))
      (node (ref "C962") (pin "1") (pinfunction "1_1") (pintype "passive"))
      (node (ref "C963") (pin "1") (pinfunction "1_1") (pintype "passive"))
      (node (ref "C964") (pin "1") (pinfunction "1_1") (pintype "passive"))
      (node (ref "C965") (pin "1") (pinfunction "1_1") (pintype "passive"))
      (node (ref "C966") (pin "1") (pinfunction "1_1") (pintype "passive"))
      (node (ref "C967") (pin "1") (pinfunction "1_1") (pintype "passive"))
      (node (ref "C968") (pin "1") (pinfunction "1_1") (pintype "passive"))
      (node (ref "C969") (pin "1") (pinfunction "1_1") (pintype "passive"))
      (node (ref "C970") (pin "1") (pinfunction "1_1") (pintype "passive"))
      (node (ref "C971") (pin "1") (pinfunction "1_1") (pintype "passive"))
      (node (ref "C972") (pin "1") (pinfunction "1_1") (pintype "passive"))
      (node (ref "C973") (pin "1") (pinfunction "1_1") (pintype "passive"))
      (node (ref "C974") (pin "1") (pinfunction "1_1") (pintype "passive"))
      (node (ref "C975") (pin "1") (pinfunction "1_1") (pintype "passive"))
      (node (ref "C976") (pin "1") (pinfunction "1_1") (pintype "passive"))
      (node (ref "C977") (pin "1") (pinfunction "1_1") (pintype "passive"))
      (node (ref "C978") (pin "1") (pinfunction "1_1") (pintype "passive"))
      (node (ref "C979") (pin "1") (pinfunction "1_1") (pintype "passive"))
      (node (ref "C980") (pin "1") (pinfunction "1_1") (pintype "passive"))
      (node (ref "C981") (pin "1") (pinfunction "1_1") (pintype "passive"))
      (node (ref "C982") (pin "1") (pinfunction "1_1") (pintype "passive"))
      (node (ref "C983") (pin "1") (pinfunction "1_1") (pintype "passive"))
      (node (ref "C984") (pin "1") (pinfunction "1_1") (pintype "passive"))
      (node (ref "C985") (pin "1") (pinfunction "1_1") (pintype "passive"))
      (node (ref "C986") (pin "1") (pinfunction "1_1") (pintype "passive"))
      (node (ref "C987") (pin "1") (pinfunction "1_1") (pintype "passive"))
      (node (ref "C988") (pin "1") (pinfunction "1_1") (pintype "passive"))
      (node (ref "C989") (pin "1") (pinfunction "1_1") (pintype "passive"))
      (node (ref "C990") (pin "1") (pinfunction "1_1") (pintype "passive"))
      (node (ref "C991") (pin "1") (pinfunction "1_1") (pintype "passive"))
      (node (ref "C992") (pin "1") (pinfunction "1_1") (pintype "passive"))
      (node (ref "FAN1") (pin "1") (pinfunction "STANDS_1") (pintype "passive"))
      (node (ref "IC72") (pin "2") (pinfunction "GND_2") (pintype "passive"))
      (node (ref "IC72") (pin "PAD") (pinfunction "PAD_PAD") (pintype "passive"))
      (node (ref "IC73") (pin "2") (pinfunction "GND_2") (pintype "passive"))
      (node (ref "IC73") (pin "PAD") (pinfunction "PAD_PAD") (pintype "passive"))
      (node (ref "IC74") (pin "2") (pinfunction "GND_2") (pintype "passive"))
      (node (ref "IC74") (pin "PAD") (pinfunction "PAD_PAD") (pintype "passive"))
      (node (ref "IC75") (pin "2") (pinfunction "GND_2") (pintype "passive"))
      (node (ref "IC75") (pin "PAD") (pinfunction "PAD_PAD") (pintype "passive"))
      (node (ref "IC76") (pin "2") (pinfunction "GND_2") (pintype "passive"))
      (node (ref "IC76") (pin "PAD") (pinfunction "PAD_PAD") (pintype "passive"))
      (node (ref "IC77") (pin "2") (pinfunction "GND_2") (pintype "passive"))
      (node (ref "IC77") (pin "PAD") (pinfunction "PAD_PAD") (pintype "passive"))
      (node (ref "IC78") (pin "2") (pinfunction "GND_2") (pintype "passive"))
      (node (ref "IC78") (pin "PAD") (pinfunction "PAD_PAD") (pintype "passive"))
      (node (ref "IC79") (pin "2") (pinfunction "GND_2") (pintype "passive"))
      (node (ref "IC79") (pin "PAD") (pinfunction "PAD_PAD") (pintype "passive"))
      (node (ref "IC80") (pin "3") (pinfunction "GND_3") (pintype "passive"))
      (node (ref "IC81") (pin "3") (pinfunction "GND_3") (pintype "passive"))
      (node (ref "MECH26") (pin "MH1") (pinfunction "MH1_MH1") (pintype "passive"))
      (node (ref "MECH27") (pin "MH1") (pinfunction "MH1_MH1") (pintype "passive"))
      (node (ref "MECH36") (pin "MH1") (pinfunction "MH1_MH1") (pintype "passive"))
      (node (ref "MECH37") (pin "MH1") (pinfunction "MH1_MH1") (pintype "passive"))
      (node (ref "R481") (pin "1") (pinfunction "1_1") (pintype "passive"))
      (node (ref "R482") (pin "1") (pinfunction "1_1") (pintype "passive"))
      (node (ref "R487") (pin "1") (pinfunction "1_1") (pintype "passive"))
      (node (ref "R488") (pin "1") (pinfunction "1_1") (pintype "passive"))
      (node (ref "R493") (pin "1") (pinfunction "1_1") (pintype "passive"))
      (node (ref "R494") (pin "1") (pinfunction "1_1") (pintype "passive"))
      (node (ref "R499") (pin "1") (pinfunction "1_1") (pintype "passive"))
      (node (ref "R500") (pin "1") (pinfunction "1_1") (pintype "passive"))
      (node (ref "R505") (pin "2") (pinfunction "2_2") (pintype "passive"))
      (node (ref "R506") (pin "2") (pinfunction "2_2") (pintype "passive"))
      (node (ref "TP1") (pin "1") (pintype "passive"))
      (node (ref "TP2") (pin "1") (pintype "passive"))
      (node (ref "TP3") (pin "1") (pintype "passive"))
      (node (ref "TP4") (pin "1") (pintype "passive"))
      (node (ref "TP5") (pin "1") (pintype "passive"))
    )
    (net (code "2") (name "Net-(IC72-ADJ)") (class "Default")
      (node (ref "IC72") (pin "5") (pinfunction "ADJ_5") (pintype "input"))
      (node (ref "R479") (pin "1") (pinfunction "1_1") (pintype "passive"))
      (node (ref "R481") (pin "2") (pinfunction "2_2") (pintype "passive"))
    )
    (net (code "3") (name "Net-(IC72-EN)") (class "Default")
      (node (ref "C954") (pin "2") (pinfunction "2_2") (pintype "passive"))
      (node (ref "FR114") (pin "2") (pinfunction "2_2") (pintype "passive"))
      (node (ref "IC72") (pin "1") (pinfunction "EN_1") (pintype "input"))
      (node (ref "IC72") (pin "6") (pinfunction "Vin_6") (pintype "input"))
    )
    (net (code "4") (name "Net-(IC72-PG)") (class "Default")
      (node (ref "C959") (pin "2") (pinfunction "2_2") (pintype "passive"))
      (node (ref "IC72") (pin "3") (pinfunction "PG_3") (pintype "output"))
    )
    (net (code "5") (name "Net-(IC72-Vout)") (class "Default")
      (node (ref "C955") (pin "2") (pinfunction "2_2") (pintype "passive"))
      (node (ref "IC72") (pin "4") (pinfunction "Vout_4") (pintype "output"))
      (node (ref "R477") (pin "2") (pinfunction "2_2") (pintype "passive"))
      (node (ref "R479") (pin "2") (pinfunction "2_2") (pintype "passive"))
    )
    (net (code "6") (name "Net-(IC73-ADJ)") (class "Default")
      (node (ref "IC73") (pin "5") (pinfunction "ADJ_5") (pintype "input"))
      (node (ref "R480") (pin "1") (pinfunction "1_1") (pintype "passive"))
      (node (ref "R482") (pin "2") (pinfunction "2_2") (pintype "passive"))
    )
    (net (code "7") (name "Net-(IC73-EN)") (class "Default")
      (node (ref "C957") (pin "2") (pinfunction "2_2") (pintype "passive"))
      (node (ref "FR115") (pin "2") (pinfunction "2_2") (pintype "passive"))
      (node (ref "IC73") (pin "1") (pinfunction "EN_1") (pintype "input"))
      (node (ref "IC73") (pin "6") (pinfunction "Vin_6") (pintype "input"))
    )
    (net (code "8") (name "Net-(IC73-PG)") (class "Default")
      (node (ref "C960") (pin "2") (pinfunction "2_2") (pintype "passive"))
      (node (ref "IC73") (pin "3") (pinfunction "PG_3") (pintype "output"))
    )
    (net (code "9") (name "Net-(IC73-Vout)") (class "Default")
      (node (ref "C958") (pin "2") (pinfunction "2_2") (pintype "passive"))
      (node (ref "IC73") (pin "4") (pinfunction "Vout_4") (pintype "output"))
      (node (ref "R478") (pin "2") (pinfunction "2_2") (pintype "passive"))
      (node (ref "R480") (pin "2") (pinfunction "2_2") (pintype "passive"))
    )
    (net (code "10") (name "Net-(IC74-ADJ)") (class "Default")
      (node (ref "IC74") (pin "5") (pinfunction "ADJ_5") (pintype "input"))
      (node (ref "R485") (pin "1") (pinfunction "1_1") (pintype "passive"))
      (node (ref "R487") (pin "2") (pinfunction "2_2") (pintype "passive"))
    )
    (net (code "11") (name "Net-(IC74-EN)") (class "Default")
      (node (ref "C962") (pin "2") (pinfunction "2_2") (pintype "passive"))
      (node (ref "FR116") (pin "2") (pinfunction "2_2") (pintype "passive"))
      (node (ref "IC74") (pin "1") (pinfunction "EN_1") (pintype "input"))
      (node (ref "IC74") (pin "6") (pinfunction "Vin_6") (pintype "input"))
    )
    (net (code "12") (name "Net-(IC74-PG)") (class "Default")
      (node (ref "C967") (pin "2") (pinfunction "2_2") (pintype "passive"))
      (node (ref "IC74") (pin "3") (pinfunction "PG_3") (pintype "output"))
    )
    (net (code "13") (name "Net-(IC74-Vout)") (class "Default")
      (node (ref "C963") (pin "2") (pinfunction "2_2") (pintype "passive"))
      (node (ref "IC74") (pin "4") (pinfunction "Vout_4") (pintype "output"))
      (node (ref "R483") (pin "2") (pinfunction "2_2") (pintype "passive"))
      (node (ref "R485") (pin "2") (pinfunction "2_2") (pintype "passive"))
    )
    (net (code "14") (name "Net-(IC75-ADJ)") (class "Default")
      (node (ref "IC75") (pin "5") (pinfunction "ADJ_5") (pintype "input"))
      (node (ref "R486") (pin "1") (pinfunction "1_1") (pintype "passive"))
      (node (ref "R488") (pin "2") (pinfunction "2_2") (pintype "passive"))
    )
    (net (code "15") (name "Net-(IC75-EN)") (class "Default")
      (node (ref "C965") (pin "2") (pinfunction "2_2") (pintype "passive"))
      (node (ref "FR117") (pin "2") (pinfunction "2_2") (pintype "passive"))
      (node (ref "IC75") (pin "1") (pinfunction "EN_1") (pintype "input"))
      (node (ref "IC75") (pin "6") (pinfunction "Vin_6") (pintype "input"))
    )
    (net (code "16") (name "Net-(IC75-PG)") (class "Default")
      (node (ref "C968") (pin "2") (pinfunction "2_2") (pintype "passive"))
      (node (ref "IC75") (pin "3") (pinfunction "PG_3") (pintype "output"))
    )
    (net (code "17") (name "Net-(IC75-Vout)") (class "Default")
      (node (ref "C966") (pin "2") (pinfunction "2_2") (pintype "passive"))
      (node (ref "IC75") (pin "4") (pinfunction "Vout_4") (pintype "output"))
      (node (ref "R484") (pin "2") (pinfunction "2_2") (pintype "passive"))
      (node (ref "R486") (pin "2") (pinfunction "2_2") (pintype "passive"))
    )
    (net (code "18") (name "Net-(IC76-ADJ)") (class "Default")
      (node (ref "IC76") (pin "5") (pinfunction "ADJ_5") (pintype "input"))
      (node (ref "R491") (pin "1") (pinfunction "1_1") (pintype "passive"))
      (node (ref "R493") (pin "2") (pinfunction "2_2") (pintype "passive"))
    )
    (net (code "19") (name "Net-(IC76-EN)") (class "Default")
      (node (ref "C970") (pin "2") (pinfunction "2_2") (pintype "passive"))
      (node (ref "FR118") (pin "2") (pinfunction "2_2") (pintype "passive"))
      (node (ref "IC76") (pin "1") (pinfunction "EN_1") (pintype "input"))
      (node (ref "IC76") (pin "6") (pinfunction "Vin_6") (pintype "input"))
    )
    (net (code "20") (name "Net-(IC76-PG)") (class "Default")
      (node (ref "C975") (pin "2") (pinfunction "2_2") (pintype "passive"))
      (node (ref "IC76") (pin "3") (pinfunction "PG_3") (pintype "output"))
    )
    (net (code "21") (name "Net-(IC76-Vout)") (class "Default")
      (node (ref "C971") (pin "2") (pinfunction "2_2") (pintype "passive"))
      (node (ref "IC76") (pin "4") (pinfunction "Vout_4") (pintype "output"))
      (node (ref "R489") (pin "2") (pinfunction "2_2") (pintype "passive"))
      (node (ref "R491") (pin "2") (pinfunction "2_2") (pintype "passive"))
    )
    (net (code "22") (name "Net-(IC77-ADJ)") (class "Default")
      (node (ref "IC77") (pin "5") (pinfunction "ADJ_5") (pintype "input"))
      (node (ref "R492") (pin "1") (pinfunction "1_1") (pintype "passive"))
      (node (ref "R494") (pin "2") (pinfunction "2_2") (pintype "passive"))
    )
    (net (code "23") (name "Net-(IC77-EN)") (class "Default")
      (node (ref "C973") (pin "2") (pinfunction "2_2") (pintype "passive"))
      (node (ref "FR119") (pin "2") (pinfunction "2_2") (pintype "passive"))
      (node (ref "IC77") (pin "1") (pinfunction "EN_1") (pintype "input"))
      (node (ref "IC77") (pin "6") (pinfunction "Vin_6") (pintype "input"))
    )
    (net (code "24") (name "Net-(IC77-PG)") (class "Default")
      (node (ref "C976") (pin "2") (pinfunction "2_2") (pintype "passive"))
      (node (ref "IC77") (pin "3") (pinfunction "PG_3") (pintype "output"))
    )
    (net (code "25") (name "Net-(IC77-Vout)") (class "Default")
      (node (ref "C974") (pin "2") (pinfunction "2_2") (pintype "passive"))
      (node (ref "IC77") (pin "4") (pinfunction "Vout_4") (pintype "output"))
      (node (ref "R490") (pin "2") (pinfunction "2_2") (pintype "passive"))
      (node (ref "R492") (pin "2") (pinfunction "2_2") (pintype "passive"))
    )
    (net (code "26") (name "Net-(IC78-ADJ)") (class "Default")
      (node (ref "IC78") (pin "5") (pinfunction "ADJ_5") (pintype "input"))
      (node (ref "R497") (pin "1") (pinfunction "1_1") (pintype "passive"))
      (node (ref "R499") (pin "2") (pinfunction "2_2") (pintype "passive"))
    )
    (net (code "27") (name "Net-(IC78-EN)") (class "Default")
      (node (ref "C978") (pin "2") (pinfunction "2_2") (pintype "passive"))
      (node (ref "FR120") (pin "2") (pinfunction "2_2") (pintype "passive"))
      (node (ref "IC78") (pin "1") (pinfunction "EN_1") (pintype "input"))
      (node (ref "IC78") (pin "6") (pinfunction "Vin_6") (pintype "input"))
    )
    (net (code "28") (name "Net-(IC78-PG)") (class "Default")
      (node (ref "C983") (pin "2") (pinfunction "2_2") (pintype "passive"))
      (node (ref "IC78") (pin "3") (pinfunction "PG_3") (pintype "output"))
    )
    (net (code "29") (name "Net-(IC78-Vout)") (class "Default")
      (node (ref "C979") (pin "2") (pinfunction "2_2") (pintype "passive"))
      (node (ref "IC78") (pin "4") (pinfunction "Vout_4") (pintype "output"))
      (node (ref "R495") (pin "2") (pinfunction "2_2") (pintype "passive"))
      (node (ref "R497") (pin "2") (pinfunction "2_2") (pintype "passive"))
    )
    (net (code "30") (name "Net-(IC79-ADJ)") (class "Default")
      (node (ref "IC79") (pin "5") (pinfunction "ADJ_5") (pintype "input"))
      (node (ref "R498") (pin "1") (pinfunction "1_1") (pintype "passive"))
      (node (ref "R500") (pin "2") (pinfunction "2_2") (pintype "passive"))
    )
    (net (code "31") (name "Net-(IC79-EN)") (class "Default")
      (node (ref "C981") (pin "2") (pinfunction "2_2") (pintype "passive"))
      (node (ref "FR121") (pin "2") (pinfunction "2_2") (pintype "passive"))
      (node (ref "IC79") (pin "1") (pinfunction "EN_1") (pintype "input"))
      (node (ref "IC79") (pin "6") (pinfunction "Vin_6") (pintype "input"))
    )
    (net (code "32") (name "Net-(IC79-PG)") (class "Default")
      (node (ref "C984") (pin "2") (pinfunction "2_2") (pintype "passive"))
      (node (ref "IC79") (pin "3") (pinfunction "PG_3") (pintype "output"))
    )
    (net (code "33") (name "Net-(IC79-Vout)") (class "Default")
      (node (ref "C982") (pin "2") (pinfunction "2_2") (pintype "passive"))
      (node (ref "IC79") (pin "4") (pinfunction "Vout_4") (pintype "output"))
      (node (ref "R496") (pin "2") (pinfunction "2_2") (pintype "passive"))
      (node (ref "R498") (pin "2") (pinfunction "2_2") (pintype "passive"))
    )
    (net (code "34") (name "Net-(IC80-ADJUST)") (class "Default")
      (node (ref "IC80") (pin "5") (pinfunction "ADJUST_5") (pintype "input"))
      (node (ref "R503") (pin "1") (pinfunction "1_1") (pintype "passive"))
      (node (ref "R505") (pin "1") (pinfunction "1_1") (pintype "passive"))
    )
    (net (code "35") (name "Net-(IC80-EN)") (class "Default")
      (node (ref "C990") (pin "2") (pinfunction "2_2") (pintype "passive"))
      (node (ref "FR122") (pin "2") (pinfunction "2_2") (pintype "passive"))
      (node (ref "IC80") (pin "1") (pinfunction "EN_1") (pintype "input"))
      (node (ref "IC80") (pin "2") (pinfunction "IN_2") (pintype "input"))
    )
    (net (code "36") (name "Net-(IC80-OUT)") (class "Default")
      (node (ref "C985") (pin "2") (pinfunction "2_2") (pintype "passive"))
      (node (ref "C986") (pin "2") (pinfunction "2_2") (pintype "passive"))
      (node (ref "IC80") (pin "4") (pinfunction "OUT_4") (pintype "output"))
      (node (ref "R501") (pin "2") (pinfunction "2_2") (pintype "passive"))
      (node (ref "R503") (pin "2") (pinfunction "2_2") (pintype "passive"))
    )
    (net (code "37") (name "Net-(IC81-ADJUST)") (class "Default")
      (node (ref "IC81") (pin "5") (pinfunction "ADJUST_5") (pintype "input"))
      (node (ref "R504") (pin "1") (pinfunction "1_1") (pintype "passive"))
      (node (ref "R506") (pin "1") (pinfunction "1_1") (pintype "passive"))
    )
    (net (code "38") (name "Net-(IC81-EN)") (class "Default")
      (node (ref "C992") (pin "2") (pinfunction "2_2") (pintype "passive"))
      (node (ref "FR123") (pin "2") (pinfunction "2_2") (pintype "passive"))
      (node (ref "IC81") (pin "1") (pinfunction "EN_1") (pintype "input"))
      (node (ref "IC81") (pin "2") (pinfunction "IN_2") (pintype "input"))
    )
    (net (code "39") (name "Net-(IC81-OUT)") (class "Default")
      (node (ref "C988") (pin "2") (pinfunction "2_2") (pintype "passive"))
      (node (ref "C989") (pin "2") (pinfunction "2_2") (pintype "passive"))
      (node (ref "IC81") (pin "4") (pinfunction "OUT_4") (pintype "output"))
      (node (ref "R502") (pin "2") (pinfunction "2_2") (pintype "passive"))
      (node (ref "R504") (pin "2") (pinfunction "2_2") (pintype "passive"))
    )
    (net (code "40") (name "VCC1P4_LMS1") (class "Default")
      (node (ref "R489") (pin "1") (pinfunction "1_1") (pintype "passive"))
    )
    (net (code "41") (name "VCC1P4_LMS2") (class "Default")
      (node (ref "R490") (pin "1") (pinfunction "1_1") (pintype "passive"))
    )
    (net (code "42") (name "VCC1P8_LMS1_A") (class "Default")
      (node (ref "R477") (pin "1") (pinfunction "1_1") (pintype "passive"))
    )
    (net (code "43") (name "VCC1P8_LMS1_B") (class "Default")
      (node (ref "R483") (pin "1") (pinfunction "1_1") (pintype "passive"))
    )
    (net (code "44") (name "VCC1P8_LMS2_A") (class "Default")
      (node (ref "R478") (pin "1") (pinfunction "1_1") (pintype "passive"))
    )
    (net (code "45") (name "VCC1P8_LMS2_B") (class "Default")
      (node (ref "R484") (pin "1") (pinfunction "1_1") (pintype "passive"))
    )
    (net (code "46") (name "VCC1P25_LMS1") (class "Default")
      (node (ref "R495") (pin "1") (pinfunction "1_1") (pintype "passive"))
    )
    (net (code "47") (name "VCC1P25_LMS1_DIG") (class "Default")
      (node (ref "R501") (pin "1") (pinfunction "1_1") (pintype "passive"))
    )
    (net (code "48") (name "VCC1P25_LMS2") (class "Default")
      (node (ref "R496") (pin "1") (pinfunction "1_1") (pintype "passive"))
    )
    (net (code "49") (name "VCC1P25_LMS2_DIG") (class "Default")
      (node (ref "R502") (pin "1") (pinfunction "1_1") (pintype "passive"))
    )
    (net (code "50") (name "VCC2P5") (class "Default")
      (node (ref "C953") (pin "2") (pinfunction "2_2") (pintype "passive"))
      (node (ref "C956") (pin "2") (pinfunction "2_2") (pintype "passive"))
      (node (ref "C961") (pin "2") (pinfunction "2_2") (pintype "passive"))
      (node (ref "C964") (pin "2") (pinfunction "2_2") (pintype "passive"))
      (node (ref "C969") (pin "2") (pinfunction "2_2") (pintype "passive"))
      (node (ref "C972") (pin "2") (pinfunction "2_2") (pintype "passive"))
      (node (ref "C977") (pin "2") (pinfunction "2_2") (pintype "passive"))
      (node (ref "C980") (pin "2") (pinfunction "2_2") (pintype "passive"))
      (node (ref "C987") (pin "2") (pinfunction "2_2") (pintype "passive"))
      (node (ref "C991") (pin "2") (pinfunction "2_2") (pintype "passive"))
      (node (ref "FR114") (pin "1") (pinfunction "1_1") (pintype "passive"))
      (node (ref "FR115") (pin "1") (pinfunction "1_1") (pintype "passive"))
      (node (ref "FR116") (pin "1") (pinfunction "1_1") (pintype "passive"))
      (node (ref "FR117") (pin "1") (pinfunction "1_1") (pintype "passive"))
      (node (ref "FR118") (pin "1") (pinfunction "1_1") (pintype "passive"))
      (node (ref "FR119") (pin "1") (pinfunction "1_1") (pintype "passive"))
      (node (ref "FR120") (pin "1") (pinfunction "1_1") (pintype "passive"))
      (node (ref "FR121") (pin "1") (pinfunction "1_1") (pintype "passive"))
      (node (ref "FR122") (pin "1") (pinfunction "1_1") (pintype "passive"))
      (node (ref "FR123") (pin "1") (pinfunction "1_1") (pintype "passive"))
    )
    (net (code "51") (name "unconnected-(F1-Pad1)") (class "Default")
      (node (ref "F1") (pin "1") (pintype "passive+no_connect"))
    )
    (net (code "52") (name "unconnected-(F2-Pad1)") (class "Default")
      (node (ref "F2") (pin "1") (pintype "passive+no_connect"))
    )
    (net (code "53") (name "unconnected-(F3-Pad1)") (class "Default")
      (node (ref "F3") (pin "1") (pintype "passive+no_connect"))
    )
    (net (code "54") (name "unconnected-(F4-Pad1)") (class "Default")
      (node (ref "F4") (pin "1") (pintype "passive+no_connect"))
    )
    (net (code "55") (name "unconnected-(F5-Pad1)") (class "Default")
      (node (ref "F5") (pin "1") (pintype "passive+no_connect"))
    )
    (net (code "56") (name "unconnected-(F6-Pad1)") (class "Default")
      (node (ref "F6") (pin "1") (pintype "passive+no_connect"))
    )
    (net (code "57") (name "unconnected-(F7-Pad1)") (class "Default")
      (node (ref "F7") (pin "1") (pintype "passive+no_connect"))
    )
    (net (code "58") (name "unconnected-(F8-Pad1)") (class "Default")
      (node (ref "F8") (pin "1") (pintype "passive+no_connect"))
    )
    (net (code "59") (name "unconnected-(FL7-Pad1)") (class "Default")
      (node (ref "FL7") (pin "1") (pintype "passive+no_connect"))
    )
    (net (code "60") (name "unconnected-(FL8-Pad1)") (class "Default")
      (node (ref "FL8") (pin "1") (pintype "passive+no_connect"))
    )
    (net (code "61") (name "unconnected-(FL9-Pad1)") (class "Default")
      (node (ref "FL9") (pin "1") (pintype "passive+no_connect"))
    )
    (net (code "62") (name "unconnected-(MECH22-PadMH1)") (class "Default")
      (node (ref "MECH22") (pin "MH1") (pinfunction "MH1_MH1") (pintype "passive+no_connect"))
    )
    (net (code "63") (name "unconnected-(MECH23-PadMH1)") (class "Default")
      (node (ref "MECH23") (pin "MH1") (pinfunction "MH1_MH1") (pintype "passive+no_connect"))
    )
    (net (code "64") (name "unconnected-(MECH24-PadMH1)") (class "Default")
      (node (ref "MECH24") (pin "MH1") (pinfunction "MH1_MH1") (pintype "passive+no_connect"))
    )
    (net (code "65") (name "unconnected-(MECH25-PadMH1)") (class "Default")
      (node (ref "MECH25") (pin "MH1") (pinfunction "MH1_MH1") (pintype "passive+no_connect"))
    )
    (net (code "66") (name "unconnected-(MECH28-PadMH1)") (class "Default")
      (node (ref "MECH28") (pin "MH1") (pinfunction "MH1_MH1") (pintype "passive+no_connect"))
    )
    (net (code "67") (name "unconnected-(MECH29-PadMH1)") (class "Default")
      (node (ref "MECH29") (pin "MH1") (pinfunction "MH1_MH1") (pintype "passive+no_connect"))
    )
    (net (code "68") (name "unconnected-(MECH30-PadMH1)") (class "Default")
      (node (ref "MECH30") (pin "MH1") (pinfunction "MH1_MH1") (pintype "passive+no_connect"))
    )
    (net (code "69") (name "unconnected-(MECH31-PadMH1)") (class "Default")
      (node (ref "MECH31") (pin "MH1") (pinfunction "MH1_MH1") (pintype "passive+no_connect"))
    )
    (net (code "70") (name "unconnected-(MECH32-PadMH1)") (class "Default")
      (node (ref "MECH32") (pin "MH1") (pinfunction "MH1_MH1") (pintype "passive+no_connect"))
    )
    (net (code "71") (name "unconnected-(MECH33-PadMH1)") (class "Default")
      (node (ref "MECH33") (pin "MH1") (pinfunction "MH1_MH1") (pintype "passive+no_connect"))
    )
    (net (code "72") (name "unconnected-(MECH34-PadMH1)") (class "Default")
      (node (ref "MECH34") (pin "MH1") (pinfunction "MH1_MH1") (pintype "passive+no_connect"))
    )
    (net (code "73") (name "unconnected-(MECH35-PadMH1)") (class "Default")
      (node (ref "MECH35") (pin "MH1") (pinfunction "MH1_MH1") (pintype "passive+no_connect"))
    )
  )
)
